# bear.net
KiCad netlist of a schematic drawn in EAGLE
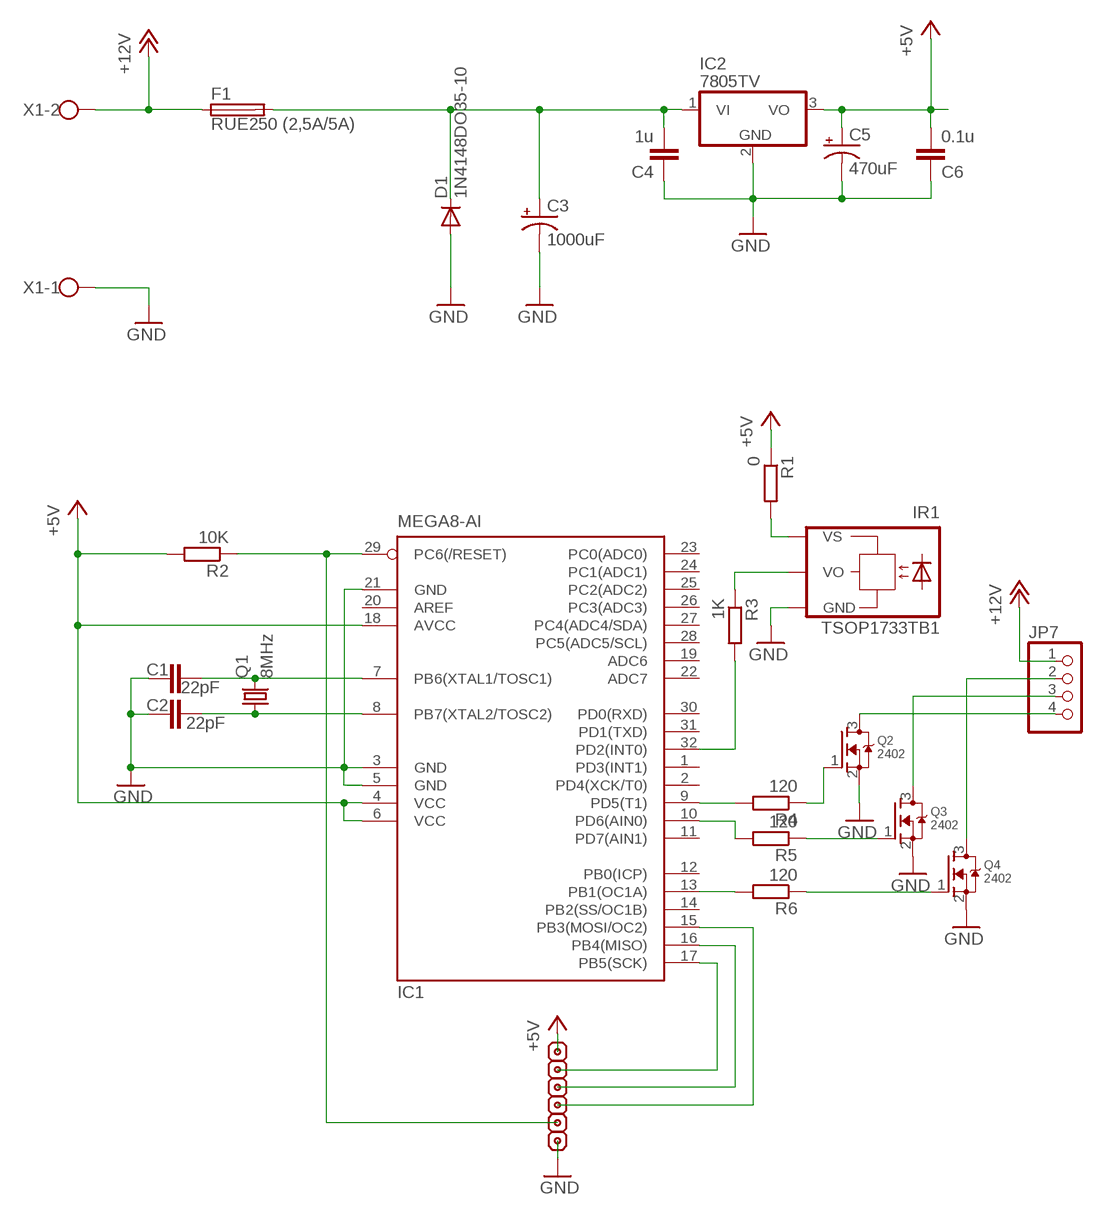
[diagram p0: schematic, sheet 1]

(export (version "E")
  (design (tool "Eeschema 10.0.6"))
  (components
    (comp (ref "C1")
      (value "22pF")
      (footprint "eagle-import:C1206")
      (libsource (lib "eagle-import") (part "C-EUC1206"))
    )
    (comp (ref "C2")
      (value "22pF")
      (footprint "eagle-import:C1206")
      (libsource (lib "eagle-import") (part "C-EUC1206"))
    )
    (comp (ref "C3")
      (value "1000uF")
      (footprint "eagle-import:E5-10,5")
      (libsource (lib "eagle-import") (part "CPOL-USE5-10.5"))
    )
    (comp (ref "C4")
      (value "1u")
      (footprint "eagle-import:C1206K")
      (libsource (lib "eagle-import") (part "C-EUC1206K"))
    )
    (comp (ref "C5")
      (value "470uF")
      (footprint "eagle-import:E5-8,5")
      (libsource (lib "eagle-import") (part "resistor_CPOL-USE5-8.5"))
    )
    (comp (ref "C6")
      (value "0.1u")
      (footprint "eagle-import:C1206K")
      (libsource (lib "eagle-import") (part "C-EUC1206K"))
    )
    (comp (ref "D1")
      (value "1N4148DO35-10")
      (footprint "eagle-import:DO35-10")
      (libsource (lib "eagle-import") (part "1N4148DO35-10"))
    )
    (comp (ref "F1")
      (value "RUE250 (2,5A/5A)")
      (footprint "eagle-import:TE5")
      (libsource (lib "eagle-import") (part "TE5"))
    )
    (comp (ref "IC1")
      (value "MEGA8-AI")
      (footprint "eagle-import:TQFP32-08")
      (fields (field (name "MPN") "ATMEGA8-16AU"))
      (libsource (lib "eagle-import") (part "MEGA8-AI"))
    )
    (comp (ref "IC2")
      (value "7805TV")
      (footprint "eagle-import:TO220V")
      (libsource (lib "eagle-import") (part "78TV05"))
    )
    (comp (ref "IR1")
      (value "TSOP1733TB1")
      (footprint "eagle-import:TSOP17_TB1")
      (libsource (lib "eagle-import") (part "TSOP17TB133"))
    )
    (comp (ref "JP7")
      (value "PINHD-1X4_2.54")
      (footprint "eagle-import:1X04")
      (libsource (lib "eagle-import") (part "PINHD-1X4_2.54"))
    )
    (comp (ref "JP_5V")
      (value "PINHD-1X1_2.54")
      (footprint "eagle-import:1X01")
      (libsource (lib "eagle-import") (part "PINHD-1X1_2.54"))
    )
    (comp (ref "JP_GND")
      (value "PINHD-1X1_2.54")
      (footprint "eagle-import:1X01")
      (libsource (lib "eagle-import") (part "PINHD-1X1_2.54"))
    )
    (comp (ref "JP_MISO")
      (value "PINHD-1X1_2.54")
      (footprint "eagle-import:1X01")
      (libsource (lib "eagle-import") (part "PINHD-1X1_2.54"))
    )
    (comp (ref "JP_MOSI")
      (value "PINHD-1X1_2.54")
      (footprint "eagle-import:1X01")
      (libsource (lib "eagle-import") (part "PINHD-1X1_2.54"))
    )
    (comp (ref "JP_RST")
      (value "PINHD-1X1_2.54")
      (footprint "eagle-import:1X01")
      (libsource (lib "eagle-import") (part "PINHD-1X1_2.54"))
    )
    (comp (ref "JP_SCK")
      (value "PINHD-1X1_2.54")
      (footprint "eagle-import:1X01")
      (libsource (lib "eagle-import") (part "PINHD-1X1_2.54"))
    )
    (comp (ref "Q1")
      (value "8MHz")
      (footprint "eagle-import:HC49_S")
      (libsource (lib "eagle-import") (part "CRYSTALHC49S"))
    )
    (comp (ref "Q2")
      (value "2402")
      (footprint "eagle-import:SOT23")
      (libsource (lib "eagle-import") (part "MOSFET-NREFLOW"))
    )
    (comp (ref "Q3")
      (value "2402")
      (footprint "eagle-import:SOT23")
      (libsource (lib "eagle-import") (part "MOSFET-NREFLOW"))
    )
    (comp (ref "Q4")
      (value "2402")
      (footprint "eagle-import:SOT23")
      (libsource (lib "eagle-import") (part "MOSFET-NREFLOW"))
    )
    (comp (ref "R1")
      (value "0")
      (footprint "eagle-import:R1206")
      (libsource (lib "eagle-import") (part "R-EU_R1206"))
    )
    (comp (ref "R2")
      (value "10K")
      (footprint "eagle-import:R1206")
      (libsource (lib "eagle-import") (part "R-EU_R1206"))
    )
    (comp (ref "R3")
      (value "1K")
      (footprint "eagle-import:R1206")
      (libsource (lib "eagle-import") (part "R-EU_R1206"))
    )
    (comp (ref "R4")
      (value "120")
      (footprint "eagle-import:R1206")
      (libsource (lib "eagle-import") (part "R-EU_R1206"))
    )
    (comp (ref "R5")
      (value "120")
      (footprint "eagle-import:R1206")
      (libsource (lib "eagle-import") (part "R-EU_R1206"))
    )
    (comp (ref "R6")
      (value "120")
      (footprint "eagle-import:R1206")
      (libsource (lib "eagle-import") (part "R-EU_R1206"))
    )
    (comp (ref "X1")
      (value "W237-102")
      (footprint "eagle-import:W237-102")
      (fields (field (name "MPN") "237-102"))
      (libsource (lib "eagle-import") (part "W237-102"))
    )
  )
  (nets
    (net (code "1") (name "+5V") (class "Default")
      (node (ref "C5") (pin "+") (pinfunction "+_+") (pintype "passive"))
      (node (ref "C6") (pin "2") (pinfunction "2_2") (pintype "passive"))
      (node (ref "IC1") (pin "18") (pinfunction "AVCC_18") (pintype "power_in"))
      (node (ref "IC1") (pin "4") (pinfunction "VCC_4") (pintype "power_in"))
      (node (ref "IC1") (pin "6") (pinfunction "VCC_6") (pintype "power_in"))
      (node (ref "IC2") (pin "3") (pinfunction "VO_3") (pintype "passive"))
      (node (ref "JP_5V") (pin "1") (pinfunction "PIN_1") (pintype "bidirectional"))
      (node (ref "R1") (pin "1") (pinfunction "1_1") (pintype "passive"))
      (node (ref "R2") (pin "2") (pinfunction "2_2") (pintype "passive"))
    )
    (net (code "2") (name "+12V") (class "Default")
      (node (ref "F1") (pin "1") (pinfunction "1_1") (pintype "passive"))
      (node (ref "JP7") (pin "1") (pinfunction "1_1") (pintype "passive"))
      (node (ref "X1") (pin "2") (pinfunction "KL_2") (pintype "passive"))
    )
    (net (code "3") (name "GND") (class "Default")
      (node (ref "C1") (pin "1") (pinfunction "1_1") (pintype "passive"))
      (node (ref "C2") (pin "1") (pinfunction "1_1") (pintype "passive"))
      (node (ref "C3") (pin "-") (pinfunction "-_-") (pintype "passive"))
      (node (ref "C4") (pin "1") (pinfunction "1_1") (pintype "passive"))
      (node (ref "C5") (pin "-") (pinfunction "-_-") (pintype "passive"))
      (node (ref "C6") (pin "1") (pinfunction "1_1") (pintype "passive"))
      (node (ref "D1") (pin "A") (pinfunction "A_A") (pintype "passive"))
      (node (ref "IC1") (pin "21") (pinfunction "GND_21") (pintype "power_in"))
      (node (ref "IC1") (pin "3") (pinfunction "GND_3") (pintype "power_in"))
      (node (ref "IC1") (pin "5") (pinfunction "GND_5") (pintype "power_in"))
      (node (ref "IC2") (pin "2") (pinfunction "GND_2") (pintype "passive"))
      (node (ref "IR1") (pin "GND") (pinfunction "GND_GND") (pintype "power_in"))
      (node (ref "JP_GND") (pin "1") (pinfunction "PIN_1") (pintype "bidirectional"))
      (node (ref "Q2") (pin "2") (pinfunction "S_2") (pintype "bidirectional"))
      (node (ref "Q3") (pin "2") (pinfunction "S_2") (pintype "bidirectional"))
      (node (ref "Q4") (pin "2") (pinfunction "S_2") (pintype "bidirectional"))
      (node (ref "X1") (pin "1") (pinfunction "KL_1") (pintype "passive"))
    )
    (net (code "4") (name "Net-(IC1-PB1(OC1A))") (class "Default")
      (node (ref "IC1") (pin "13") (pinfunction "PB1(OC1A)_13") (pintype "bidirectional"))
      (node (ref "R6") (pin "2") (pinfunction "2_2") (pintype "passive"))
    )
    (net (code "5") (name "Net-(IC1-PB3(MOSI{slash}OC2))") (class "Default")
      (node (ref "IC1") (pin "15") (pinfunction "PB3(MOSI/OC2)_15") (pintype "bidirectional"))
      (node (ref "JP_MOSI") (pin "1") (pinfunction "PIN_1") (pintype "bidirectional"))
    )
    (net (code "6") (name "Net-(IC1-PB4(MISO))") (class "Default")
      (node (ref "IC1") (pin "16") (pinfunction "PB4(MISO)_16") (pintype "bidirectional"))
      (node (ref "JP_MISO") (pin "1") (pinfunction "PIN_1") (pintype "bidirectional"))
    )
    (net (code "7") (name "Net-(IC1-PB5(SCK))") (class "Default")
      (node (ref "IC1") (pin "17") (pinfunction "PB5(SCK)_17") (pintype "bidirectional"))
      (node (ref "JP_SCK") (pin "1") (pinfunction "PIN_1") (pintype "bidirectional"))
    )
    (net (code "8") (name "Net-(IC1-PB6(XTAL1{slash}TOSC1))") (class "Default")
      (node (ref "C1") (pin "2") (pinfunction "2_2") (pintype "passive"))
      (node (ref "IC1") (pin "7") (pinfunction "PB6(XTAL1/TOSC1)_7") (pintype "bidirectional"))
      (node (ref "Q1") (pin "2") (pinfunction "2_2") (pintype "passive"))
    )
    (net (code "9") (name "Net-(IC1-PB7(XTAL2{slash}TOSC2))") (class "Default")
      (node (ref "C2") (pin "2") (pinfunction "2_2") (pintype "passive"))
      (node (ref "IC1") (pin "8") (pinfunction "PB7(XTAL2/TOSC2)_8") (pintype "bidirectional"))
      (node (ref "Q1") (pin "1") (pinfunction "1_1") (pintype "passive"))
    )
    (net (code "10") (name "Net-(IC1-PC6({slash}RESET))") (class "Default")
      (node (ref "IC1") (pin "29") (pinfunction "PC6(/RESET)_29") (pintype "bidirectional"))
      (node (ref "JP_RST") (pin "1") (pinfunction "PIN_1") (pintype "bidirectional"))
      (node (ref "R2") (pin "1") (pinfunction "1_1") (pintype "passive"))
    )
    (net (code "11") (name "Net-(IC1-PD2(INT0))") (class "Default")
      (node (ref "IC1") (pin "32") (pinfunction "PD2(INT0)_32") (pintype "bidirectional"))
      (node (ref "R3") (pin "2") (pinfunction "2_2") (pintype "passive"))
    )
    (net (code "12") (name "Net-(IC1-PD5(T1))") (class "Default")
      (node (ref "IC1") (pin "9") (pinfunction "PD5(T1)_9") (pintype "bidirectional"))
      (node (ref "R4") (pin "2") (pinfunction "2_2") (pintype "passive"))
    )
    (net (code "13") (name "Net-(IC1-PD6(AIN0))") (class "Default")
      (node (ref "IC1") (pin "10") (pinfunction "PD6(AIN0)_10") (pintype "bidirectional"))
      (node (ref "R5") (pin "2") (pinfunction "2_2") (pintype "passive"))
    )
    (net (code "14") (name "Net-(IC2-VI)") (class "Default")
      (node (ref "C3") (pin "+") (pinfunction "+_+") (pintype "passive"))
      (node (ref "C4") (pin "2") (pinfunction "2_2") (pintype "passive"))
      (node (ref "D1") (pin "C") (pinfunction "C_C") (pintype "passive"))
      (node (ref "F1") (pin "2") (pinfunction "2_2") (pintype "passive"))
      (node (ref "IC2") (pin "1") (pinfunction "VI_1") (pintype "input"))
    )
    (net (code "15") (name "Net-(IR1-PadVO)") (class "Default")
      (node (ref "IR1") (pin "VO") (pinfunction "VO_VO") (pintype "open_collector"))
      (node (ref "R3") (pin "1") (pinfunction "1_1") (pintype "passive"))
    )
    (net (code "16") (name "Net-(IR1-PadVS)") (class "Default")
      (node (ref "IR1") (pin "VS") (pinfunction "VS_VS") (pintype "power_in"))
      (node (ref "R1") (pin "2") (pinfunction "2_2") (pintype "passive"))
    )
    (net (code "17") (name "Net-(Q2-D)") (class "Default")
      (node (ref "JP7") (pin "4") (pinfunction "4_4") (pintype "passive"))
      (node (ref "Q2") (pin "3") (pinfunction "D_3") (pintype "bidirectional"))
    )
    (net (code "18") (name "Net-(Q2-G)") (class "Default")
      (node (ref "Q2") (pin "1") (pinfunction "G_1") (pintype "bidirectional"))
      (node (ref "R4") (pin "1") (pinfunction "1_1") (pintype "passive"))
    )
    (net (code "19") (name "Net-(Q3-D)") (class "Default")
      (node (ref "JP7") (pin "3") (pinfunction "3_3") (pintype "passive"))
      (node (ref "Q3") (pin "3") (pinfunction "D_3") (pintype "bidirectional"))
    )
    (net (code "20") (name "Net-(Q3-G)") (class "Default")
      (node (ref "Q3") (pin "1") (pinfunction "G_1") (pintype "bidirectional"))
      (node (ref "R5") (pin "1") (pinfunction "1_1") (pintype "passive"))
    )
    (net (code "21") (name "Net-(Q4-D)") (class "Default")
      (node (ref "JP7") (pin "2") (pinfunction "2_2") (pintype "passive"))
      (node (ref "Q4") (pin "3") (pinfunction "D_3") (pintype "bidirectional"))
    )
    (net (code "22") (name "Net-(Q4-G)") (class "Default")
      (node (ref "Q4") (pin "1") (pinfunction "G_1") (pintype "bidirectional"))
      (node (ref "R6") (pin "1") (pinfunction "1_1") (pintype "passive"))
    )
    (net (code "23") (name "unconnected-(IC1-ADC6-Pad19)") (class "Default")
      (node (ref "IC1") (pin "19") (pinfunction "ADC6_19") (pintype "bidirectional"))
    )
    (net (code "24") (name "unconnected-(IC1-ADC7-Pad22)") (class "Default")
      (node (ref "IC1") (pin "22") (pinfunction "ADC7_22") (pintype "bidirectional"))
    )
    (net (code "25") (name "unconnected-(IC1-AREF-Pad20)") (class "Default")
      (node (ref "IC1") (pin "20") (pinfunction "AREF_20") (pintype "passive"))
    )
    (net (code "26") (name "unconnected-(IC1-PB0(ICP)-Pad12)") (class "Default")
      (node (ref "IC1") (pin "12") (pinfunction "PB0(ICP)_12") (pintype "bidirectional"))
    )
    (net (code "27") (name "unconnected-(IC1-PB2(SS{slash}OC1B)-Pad14)") (class "Default")
      (node (ref "IC1") (pin "14") (pinfunction "PB2(SS/OC1B)_14") (pintype "bidirectional"))
    )
    (net (code "28") (name "unconnected-(IC1-PC0(ADC0)-Pad23)") (class "Default")
      (node (ref "IC1") (pin "23") (pinfunction "PC0(ADC0)_23") (pintype "bidirectional"))
    )
    (net (code "29") (name "unconnected-(IC1-PC1(ADC1)-Pad24)") (class "Default")
      (node (ref "IC1") (pin "24") (pinfunction "PC1(ADC1)_24") (pintype "bidirectional"))
    )
    (net (code "30") (name "unconnected-(IC1-PC2(ADC2)-Pad25)") (class "Default")
      (node (ref "IC1") (pin "25") (pinfunction "PC2(ADC2)_25") (pintype "bidirectional"))
    )
    (net (code "31") (name "unconnected-(IC1-PC3(ADC3)-Pad26)") (class "Default")
      (node (ref "IC1") (pin "26") (pinfunction "PC3(ADC3)_26") (pintype "bidirectional"))
    )
    (net (code "32") (name "unconnected-(IC1-PC4(ADC4{slash}SDA)-Pad27)") (class "Default")
      (node (ref "IC1") (pin "27") (pinfunction "PC4(ADC4/SDA)_27") (pintype "bidirectional"))
    )
    (net (code "33") (name "unconnected-(IC1-PC5(ADC5{slash}SCL)-Pad28)") (class "Default")
      (node (ref "IC1") (pin "28") (pinfunction "PC5(ADC5/SCL)_28") (pintype "bidirectional"))
    )
    (net (code "34") (name "unconnected-(IC1-PD0(RXD)-Pad30)") (class "Default")
      (node (ref "IC1") (pin "30") (pinfunction "PD0(RXD)_30") (pintype "bidirectional"))
    )
    (net (code "35") (name "unconnected-(IC1-PD1(TXD)-Pad31)") (class "Default")
      (node (ref "IC1") (pin "31") (pinfunction "PD1(TXD)_31") (pintype "bidirectional"))
    )
    (net (code "36") (name "unconnected-(IC1-PD3(INT1)-Pad1)") (class "Default")
      (node (ref "IC1") (pin "1") (pinfunction "PD3(INT1)_1") (pintype "bidirectional"))
    )
    (net (code "37") (name "unconnected-(IC1-PD4(XCK{slash}T0)-Pad2)") (class "Default")
      (node (ref "IC1") (pin "2") (pinfunction "PD4(XCK/T0)_2") (pintype "bidirectional"))
    )
    (net (code "38") (name "unconnected-(IC1-PD7(AIN1)-Pad11)") (class "Default")
      (node (ref "IC1") (pin "11") (pinfunction "PD7(AIN1)_11") (pintype "bidirectional"))
    )
  )
)
